# MIXR_Power_-_Port_Expander.net
KiCad netlist of a schematic drawn in Altium Designer
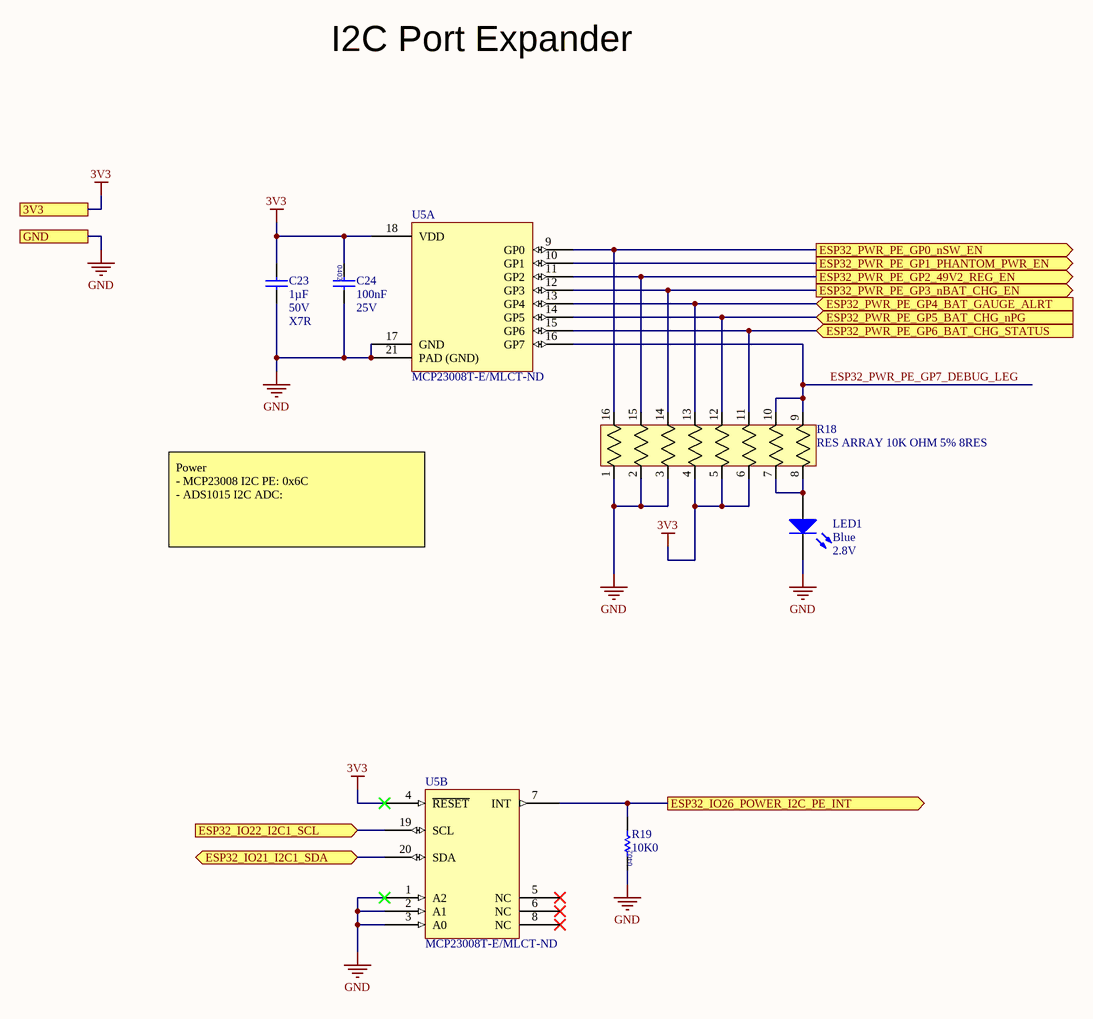
[diagram p0: MIXR Power - Port Expander.SchDoc]

(export (version "E")
  (design (tool "Eeschema 10.0.6"))
  (components
    (comp (ref "C23")
      (value "CAP CER 1UF 50V 10% X7R 0603")
      (footprint "CAP, 0603")
      (description "1µF ±10% 50V Ceramic Capacitor X7R 0603 (1608 Metric)")
      (fields
        (field (name "TOLERANCE") "±10%")
        (field (name "CAPACITANCE") "1µF")
        (field (name "VOLTAGE") "50V")
        (field (name "TEMPERATURE COEFFICIENT") "X7R")
      )
      (libsource (lib "Schematic Diagrams") (part "CAP CER 1UF 50V 10% X7R 0603"))
    )
    (comp (ref "C24")
      (value "CAP CER 0.1UF 16V X7R 0402")
      (footprint "CAP 0402")
      (description "Cap Ceramic 0.1uF 25V X7R 10% SMD 0402 125C Paper T/R")
      (fields
        (field (name "TOLERANCE") "10%")
        (field (name "CAPACITANCE") "100nF")
        (field (name "VOLTAGE") "25V")
        (field (name "MANUFACTURER") "Murata")
      )
      (libsource (lib "Schematic Diagrams") (part "CAP CER 0.1UF 16V X7R 0402"))
    )
    (comp (ref "LED1")
      (value "LED BLUE CLEAR 2.8V 0603")
      (footprint "LED_0603")
      (description "Blue 470nm LED Indication - Discrete 2.8V 0603 (1608 Metric)")
      (fields (field (name "COLOR") "Blue") (field (name "VOLTAGE - FORWARD (VF) (TYP)") "2.8V"))
      (libsource (lib "Schematic Diagrams") (part "LED BLUE CLEAR 2.8V 0603"))
    )
    (comp (ref "R18")
      (value "RES ARRAY 10K OHM 5% 8RES")
      (footprint "RES ARRAY, 8 POS 1506")
      (description "RES ARRAY SMD 10K 5% 62.5mW 1506")
      (fields
        (field (name "MANUFACTURER_PART_NUMBER") "EXB-2HV103JV")
        (field (name "MANUFACTURER") "Panasonic Electronic Components")
        (field (name "COPYRIGHT") "Copyright (C) 2015 Accelerated Designs. All rights reserved")
      )
      (libsource (lib "Schematic Diagrams") (part "RES ARRAY 10K OHM 5% 8RES EXB-2HV103JV"))
    )
    (comp (ref "R19")
      (value "RES 10K OHM 1% 1/16W 0402")
      (footprint "RES 0402")
      (description "Surface Mount Thick Film Resistor, Rc Series, 10 Kohm, 62.5 Mw, - 1%, 50 V, 0402 [1005 Metric]")
      (fields
        (field (name "TOLERANCE") "1%")
        (field (name "RESISTANCE") "10K0")
        (field (name "MANUFACTURER") "Yageo")
      )
      (libsource (lib "Schematic Diagrams") (part "RES 10K OHM 1% 1/16W 0402"))
    )
    (comp (ref "U5")
      (value "MCP23008")
      (footprint "QFN50P400X400X100_HS-21M")
      (description "I/O Expander 8 I²C 1.7MHz 20-QFN-EP (4x4)")
      (fields (field (name "SUPPLIER PART NUMBER 1") "MCP23008T-E/MLCT-ND"))
      (libsource (lib "Schematic Diagrams") (part "IC I/O EXPANDER I2C 8CH 20 QFN"))
    )
  )
  (nets
    (net (code "1") (name "/ESP32_IO21_I2C1_SDA") (class "Default")
      (node (ref "U5") (pin "20") (pinfunction "SDA_20") (pintype "bidirectional"))
    )
    (net (code "2") (name "/ESP32_IO22_I2C1_SCL") (class "Default")
      (node (ref "U5") (pin "19") (pinfunction "SCL_19") (pintype "bidirectional"))
    )
    (net (code "3") (name "/ESP32_IO26_POWER_I2C_PE_INT") (class "Default")
      (node (ref "R19") (pin "2") (pinfunction "2_2") (pintype "passive"))
      (node (ref "U5") (pin "7") (pinfunction "INT_7") (pintype "output"))
    )
    (net (code "4") (name "/ESP32_PWR_PE_GP0_nSW_EN") (class "Default")
      (node (ref "R18") (pin "16") (pinfunction "16_16") (pintype "passive"))
      (node (ref "U5") (pin "9") (pinfunction "GP0_9") (pintype "bidirectional"))
    )
    (net (code "5") (name "/ESP32_PWR_PE_GP1_PHANTOM_PWR_EN") (class "Default")
      (node (ref "U5") (pin "10") (pinfunction "GP1_10") (pintype "bidirectional"))
    )
    (net (code "6") (name "/ESP32_PWR_PE_GP2_49V2_REG_EN") (class "Default")
      (node (ref "R18") (pin "15") (pinfunction "15_15") (pintype "passive"))
      (node (ref "U5") (pin "11") (pinfunction "GP2_11") (pintype "bidirectional"))
    )
    (net (code "7") (name "/ESP32_PWR_PE_GP3_nBAT_CHG_EN") (class "Default")
      (node (ref "R18") (pin "14") (pinfunction "14_14") (pintype "passive"))
      (node (ref "U5") (pin "12") (pinfunction "GP3_12") (pintype "bidirectional"))
    )
    (net (code "8") (name "/ESP32_PWR_PE_GP4_BAT_GAUGE_ALRT") (class "Default")
      (node (ref "R18") (pin "13") (pinfunction "13_13") (pintype "passive"))
      (node (ref "U5") (pin "13") (pinfunction "GP4_13") (pintype "bidirectional"))
    )
    (net (code "9") (name "/ESP32_PWR_PE_GP5_BAT_CHG_nPG") (class "Default")
      (node (ref "R18") (pin "12") (pinfunction "12_12") (pintype "passive"))
      (node (ref "U5") (pin "14") (pinfunction "GP5_14") (pintype "bidirectional"))
    )
    (net (code "10") (name "/ESP32_PWR_PE_GP6_BAT_CHG_STATUS") (class "Default")
      (node (ref "R18") (pin "11") (pinfunction "11_11") (pintype "passive"))
      (node (ref "U5") (pin "15") (pinfunction "GP6_15") (pintype "bidirectional"))
    )
    (net (code "11") (name "/ESP32_PWR_PE_GP7_DEBUG_LEG") (class "Default")
      (node (ref "R18") (pin "10") (pinfunction "10_10") (pintype "passive"))
      (node (ref "R18") (pin "9") (pinfunction "9_9") (pintype "passive"))
      (node (ref "U5") (pin "16") (pinfunction "GP7_16") (pintype "bidirectional"))
    )
    (net (code "12") (name "3V3") (class "Default")
      (node (ref "C23") (pin "1") (pinfunction "1_1") (pintype "passive"))
      (node (ref "C24") (pin "1") (pinfunction "1_1") (pintype "passive"))
      (node (ref "R18") (pin "4") (pinfunction "4_4") (pintype "passive"))
      (node (ref "R18") (pin "5") (pinfunction "5_5") (pintype "passive"))
      (node (ref "R18") (pin "6") (pinfunction "6_6") (pintype "passive"))
      (node (ref "U5") (pin "18") (pinfunction "VDD_18") (pintype "power_in"))
      (node (ref "U5") (pin "4") (pinfunction "~{RESET}_4") (pintype "input"))
    )
    (net (code "13") (name "GND") (class "Default")
      (node (ref "C23") (pin "2") (pinfunction "2_2") (pintype "passive"))
      (node (ref "C24") (pin "2") (pinfunction "2_2") (pintype "passive"))
      (node (ref "LED1") (pin "2") (pinfunction "K_2") (pintype "passive"))
      (node (ref "R18") (pin "1") (pinfunction "1_1") (pintype "passive"))
      (node (ref "R18") (pin "2") (pinfunction "2_2") (pintype "passive"))
      (node (ref "R18") (pin "3") (pinfunction "3_3") (pintype "passive"))
      (node (ref "R19") (pin "1") (pinfunction "1_1") (pintype "passive"))
      (node (ref "U5") (pin "1") (pinfunction "A2_1") (pintype "input"))
      (node (ref "U5") (pin "17") (pinfunction "GND_17") (pintype "power_in"))
      (node (ref "U5") (pin "2") (pinfunction "A1_2") (pintype "input"))
      (node (ref "U5") (pin "21") (pinfunction "PAD_(GND)_21") (pintype "power_in"))
      (node (ref "U5") (pin "3") (pinfunction "A0_3") (pintype "input"))
    )
    (net (code "14") (name "Net-(LED1-A)") (class "Default")
      (node (ref "LED1") (pin "1") (pinfunction "A_1") (pintype "passive"))
      (node (ref "R18") (pin "7") (pinfunction "7_7") (pintype "passive"))
      (node (ref "R18") (pin "8") (pinfunction "8_8") (pintype "passive"))
    )
    (net (code "15") (name "unconnected-(U5B-NC-Pad5)") (class "Default")
      (node (ref "U5") (pin "5") (pinfunction "NC_5") (pintype "passive+no_connect"))
    )
    (net (code "16") (name "unconnected-(U5B-NC-Pad6)") (class "Default")
      (node (ref "U5") (pin "6") (pinfunction "NC_6") (pintype "passive+no_connect"))
    )
    (net (code "17") (name "unconnected-(U5B-NC-Pad8)") (class "Default")
      (node (ref "U5") (pin "8") (pinfunction "NC_8") (pintype "passive+no_connect"))
    )
  )
)
